# Sheet2.net
KiCad netlist of a schematic drawn in Altium Designer
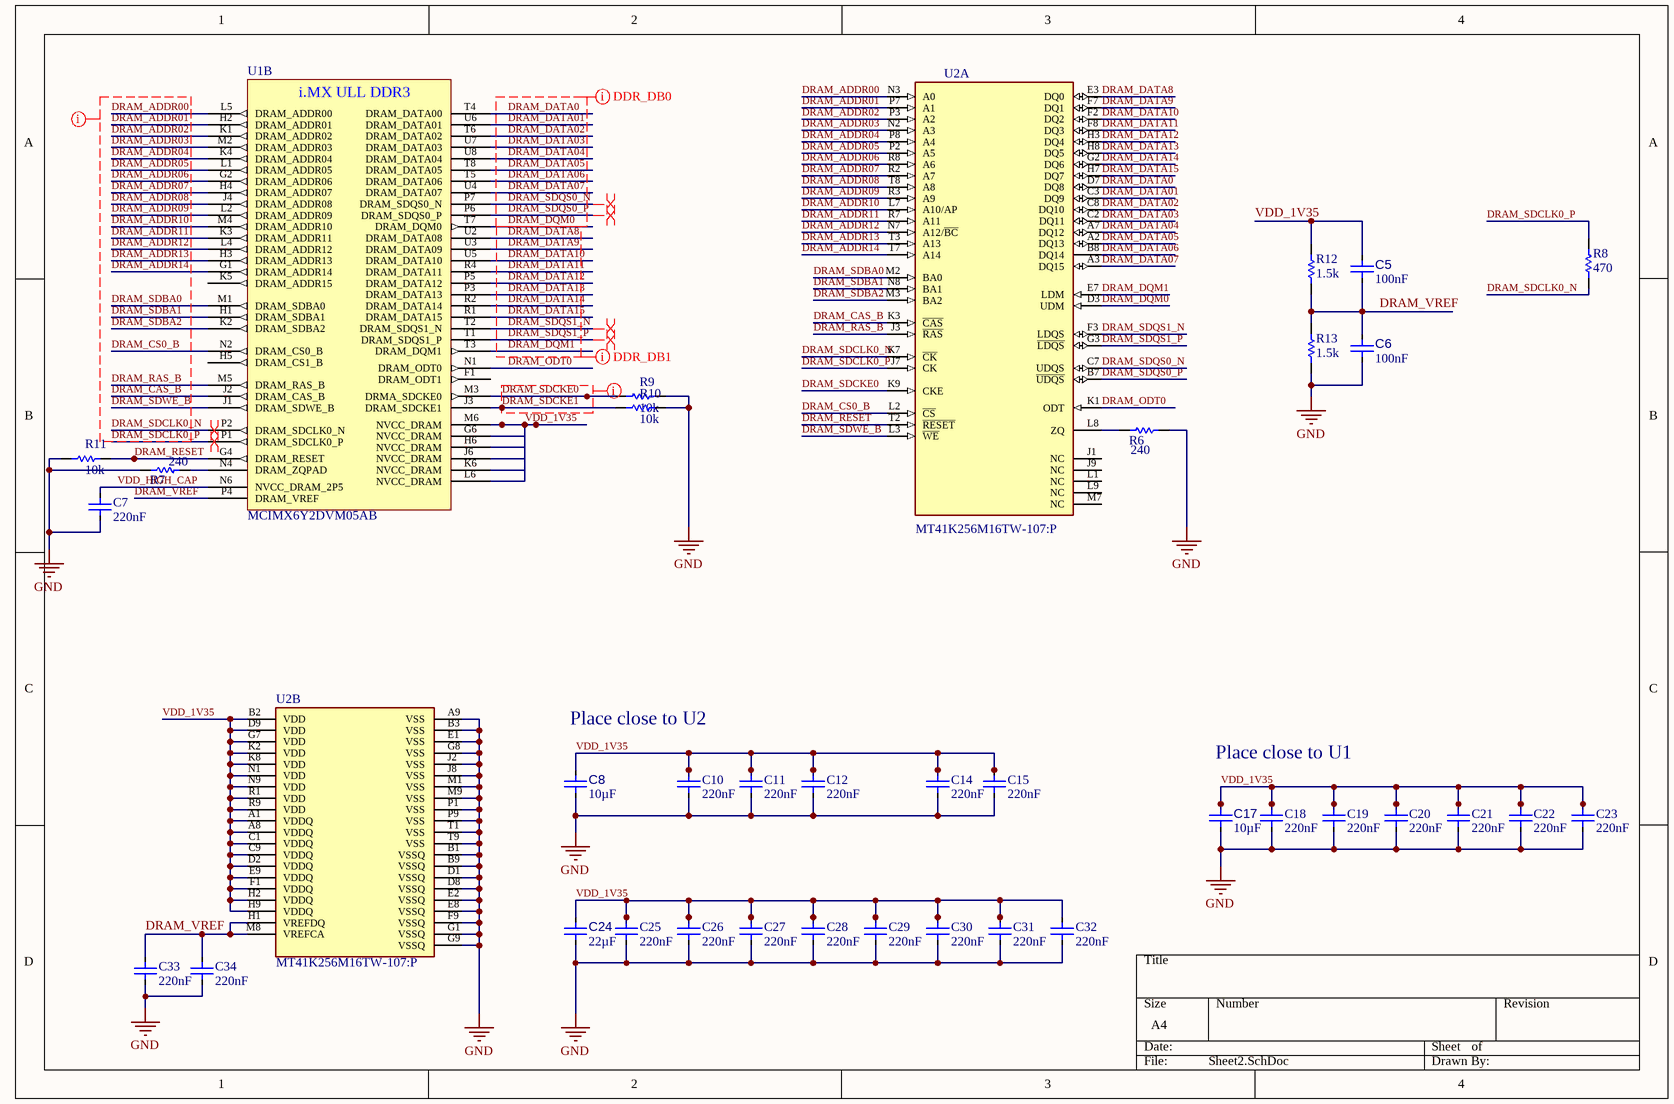
[diagram p0: Sheet2.SchDoc]

(export (version "E")
  (design (tool "Eeschema 10.0.6"))
  (components
    (comp (ref "C5")
      (value "100nF")
      (footprint "0402-SMD-CAP")
      (description "Chip Capacitor, 0.1 uF, +/- 5%, 16 V, 0402 (1005 Metric)")
      (fields (field (name "TOLERANCE") "5%") (field (name "MFR. PART NO.") "EMF105B7104MVHF"))
      (libsource (lib "Budapest University of Technology and Economics") (part "CAP-NP-2"))
    )
    (comp (ref "C6")
      (value "100nF")
      (footprint "0402-SMD-CAP")
      (description "Chip Capacitor, 0.1 uF, +/- 5%, 16 V, 0402 (1005 Metric)")
      (fields (field (name "TOLERANCE") "5%") (field (name "MFR. PART NO.") "EMF105B7104MVHF"))
      (libsource (lib "Budapest University of Technology and Economics") (part "CAP-NP-2"))
    )
    (comp (ref "C7")
      (value "220nF")
      (footprint "0402-SMD-CAP")
      (description "Chip Capacitor, 220nF +/-20%, 10V, 0402, Thickness 0.6 mm")
      (fields (field (name "TOLERANCE") "10%") (field (name "MFR. PART NO.") "0402ZD224KAT2A"))
      (libsource (lib "Budapest University of Technology and Economics") (part "b4654b650e69147ec39a6b967a45e02"))
    )
    (comp (ref "C8")
      (value "10µF")
      (footprint "0603-SMD-CAP")
      (description "Chip Capacitor, 10µF +/-20%, 10V, 0603, Thickness 1 mm")
      (fields (field (name "TOLERANCE") "10%") (field (name "MFR. PART NO.") "0603ZD106KAT2A"))
      (libsource (lib "Budapest University of Technology and Economics") (part "CAP-NP-2"))
    )
    (comp (ref "C10")
      (value "220nF")
      (footprint "0402-SMD-CAP")
      (description "Chip Capacitor, 220nF +/-20%, 10V, 0402, Thickness 0.6 mm")
      (fields (field (name "TOLERANCE") "10%") (field (name "MFR. PART NO.") "0402ZD224KAT2A"))
      (libsource (lib "Budapest University of Technology and Economics") (part "b4654b650e69147ec39a6b967a45e02"))
    )
    (comp (ref "C11")
      (value "220nF")
      (footprint "0402-SMD-CAP")
      (description "Chip Capacitor, 220nF +/-20%, 10V, 0402, Thickness 0.6 mm")
      (fields (field (name "TOLERANCE") "10%") (field (name "MFR. PART NO.") "0402ZD224KAT2A"))
      (libsource (lib "Budapest University of Technology and Economics") (part "b4654b650e69147ec39a6b967a45e02"))
    )
    (comp (ref "C12")
      (value "220nF")
      (footprint "0402-SMD-CAP")
      (description "Chip Capacitor, 220nF +/-20%, 10V, 0402, Thickness 0.6 mm")
      (fields (field (name "TOLERANCE") "10%") (field (name "MFR. PART NO.") "0402ZD224KAT2A"))
      (libsource (lib "Budapest University of Technology and Economics") (part "b4654b650e69147ec39a6b967a45e02"))
    )
    (comp (ref "C14")
      (value "220nF")
      (footprint "0402-SMD-CAP")
      (description "Chip Capacitor, 220nF +/-20%, 10V, 0402, Thickness 0.6 mm")
      (fields (field (name "TOLERANCE") "10%") (field (name "MFR. PART NO.") "0402ZD224KAT2A"))
      (libsource (lib "Budapest University of Technology and Economics") (part "b4654b650e69147ec39a6b967a45e02"))
    )
    (comp (ref "C15")
      (value "220nF")
      (footprint "0402-SMD-CAP")
      (description "Chip Capacitor, 220nF +/-20%, 10V, 0402, Thickness 0.6 mm")
      (fields (field (name "TOLERANCE") "10%") (field (name "MFR. PART NO.") "0402ZD224KAT2A"))
      (libsource (lib "Budapest University of Technology and Economics") (part "b4654b650e69147ec39a6b967a45e02"))
    )
    (comp (ref "C17")
      (value "10µF")
      (footprint "0603-SMD-CAP")
      (description "Chip Capacitor, 10µF +/-20%, 10V, 0603, Thickness 1 mm")
      (fields (field (name "TOLERANCE") "10%") (field (name "MFR. PART NO.") "0603ZD106KAT2A"))
      (libsource (lib "Budapest University of Technology and Economics") (part "CAP-NP-2"))
    )
    (comp (ref "C18")
      (value "220nF")
      (footprint "0402-SMD-CAP")
      (description "Chip Capacitor, 220nF +/-20%, 10V, 0402, Thickness 0.6 mm")
      (fields (field (name "TOLERANCE") "10%") (field (name "MFR. PART NO.") "0402ZD224KAT2A"))
      (libsource (lib "Budapest University of Technology and Economics") (part "b4654b650e69147ec39a6b967a45e02"))
    )
    (comp (ref "C19")
      (value "220nF")
      (footprint "0402-SMD-CAP")
      (description "Chip Capacitor, 220nF +/-20%, 10V, 0402, Thickness 0.6 mm")
      (fields (field (name "TOLERANCE") "10%") (field (name "MFR. PART NO.") "0402ZD224KAT2A"))
      (libsource (lib "Budapest University of Technology and Economics") (part "b4654b650e69147ec39a6b967a45e02"))
    )
    (comp (ref "C20")
      (value "220nF")
      (footprint "0402-SMD-CAP")
      (description "Chip Capacitor, 220nF +/-20%, 10V, 0402, Thickness 0.6 mm")
      (fields (field (name "TOLERANCE") "10%") (field (name "MFR. PART NO.") "0402ZD224KAT2A"))
      (libsource (lib "Budapest University of Technology and Economics") (part "b4654b650e69147ec39a6b967a45e02"))
    )
    (comp (ref "C21")
      (value "220nF")
      (footprint "0402-SMD-CAP")
      (description "Chip Capacitor, 220nF +/-20%, 10V, 0402, Thickness 0.6 mm")
      (fields (field (name "TOLERANCE") "10%") (field (name "MFR. PART NO.") "0402ZD224KAT2A"))
      (libsource (lib "Budapest University of Technology and Economics") (part "b4654b650e69147ec39a6b967a45e02"))
    )
    (comp (ref "C22")
      (value "220nF")
      (footprint "0402-SMD-CAP")
      (description "Chip Capacitor, 220nF +/-20%, 10V, 0402, Thickness 0.6 mm")
      (fields (field (name "TOLERANCE") "10%") (field (name "MFR. PART NO.") "0402ZD224KAT2A"))
      (libsource (lib "Budapest University of Technology and Economics") (part "b4654b650e69147ec39a6b967a45e02"))
    )
    (comp (ref "C23")
      (value "220nF")
      (footprint "0402-SMD-CAP")
      (description "Chip Capacitor, 220nF +/-20%, 10V, 0402, Thickness 0.6 mm")
      (fields (field (name "TOLERANCE") "10%") (field (name "MFR. PART NO.") "0402ZD224KAT2A"))
      (libsource (lib "Budapest University of Technology and Economics") (part "b4654b650e69147ec39a6b967a45e02"))
    )
    (comp (ref "C24")
      (value "22µF")
      (footprint "0805-SMD-CAP")
      (description "Chip Capacitor, 22µF +/-40%, 16V, 0805, Thickness 1.45 mm")
      (fields (field (name "TOLERANCE") "5%") (field (name "MFR. PART NO.") "CL21A226MOQNNNE"))
      (libsource (lib "Budapest University of Technology and Economics") (part "CAP-NP-2"))
    )
    (comp (ref "C25")
      (value "220nF")
      (footprint "0402-SMD-CAP")
      (description "Chip Capacitor, 220nF +/-20%, 10V, 0402, Thickness 0.6 mm")
      (fields (field (name "TOLERANCE") "10%") (field (name "MFR. PART NO.") "0402ZD224KAT2A"))
      (libsource (lib "Budapest University of Technology and Economics") (part "b4654b650e69147ec39a6b967a45e02"))
    )
    (comp (ref "C26")
      (value "220nF")
      (footprint "0402-SMD-CAP")
      (description "Chip Capacitor, 220nF +/-20%, 10V, 0402, Thickness 0.6 mm")
      (fields (field (name "TOLERANCE") "10%") (field (name "MFR. PART NO.") "0402ZD224KAT2A"))
      (libsource (lib "Budapest University of Technology and Economics") (part "b4654b650e69147ec39a6b967a45e02"))
    )
    (comp (ref "C27")
      (value "220nF")
      (footprint "0402-SMD-CAP")
      (description "Chip Capacitor, 220nF +/-20%, 10V, 0402, Thickness 0.6 mm")
      (fields (field (name "TOLERANCE") "10%") (field (name "MFR. PART NO.") "0402ZD224KAT2A"))
      (libsource (lib "Budapest University of Technology and Economics") (part "b4654b650e69147ec39a6b967a45e02"))
    )
    (comp (ref "C28")
      (value "220nF")
      (footprint "0402-SMD-CAP")
      (description "Chip Capacitor, 220nF +/-20%, 10V, 0402, Thickness 0.6 mm")
      (fields (field (name "TOLERANCE") "10%") (field (name "MFR. PART NO.") "0402ZD224KAT2A"))
      (libsource (lib "Budapest University of Technology and Economics") (part "b4654b650e69147ec39a6b967a45e02"))
    )
    (comp (ref "C29")
      (value "220nF")
      (footprint "0402-SMD-CAP")
      (description "Chip Capacitor, 220nF +/-20%, 10V, 0402, Thickness 0.6 mm")
      (fields (field (name "TOLERANCE") "10%") (field (name "MFR. PART NO.") "0402ZD224KAT2A"))
      (libsource (lib "Budapest University of Technology and Economics") (part "b4654b650e69147ec39a6b967a45e02"))
    )
    (comp (ref "C30")
      (value "220nF")
      (footprint "0402-SMD-CAP")
      (description "Chip Capacitor, 220nF +/-20%, 10V, 0402, Thickness 0.6 mm")
      (fields (field (name "TOLERANCE") "10%") (field (name "MFR. PART NO.") "0402ZD224KAT2A"))
      (libsource (lib "Budapest University of Technology and Economics") (part "b4654b650e69147ec39a6b967a45e02"))
    )
    (comp (ref "C31")
      (value "220nF")
      (footprint "0402-SMD-CAP")
      (description "Chip Capacitor, 220nF +/-20%, 10V, 0402, Thickness 0.6 mm")
      (fields (field (name "TOLERANCE") "10%") (field (name "MFR. PART NO.") "0402ZD224KAT2A"))
      (libsource (lib "Budapest University of Technology and Economics") (part "b4654b650e69147ec39a6b967a45e02"))
    )
    (comp (ref "C32")
      (value "220nF")
      (footprint "0402-SMD-CAP")
      (description "Chip Capacitor, 220nF +/-20%, 10V, 0402, Thickness 0.6 mm")
      (fields (field (name "TOLERANCE") "10%") (field (name "MFR. PART NO.") "0402ZD224KAT2A"))
      (libsource (lib "Budapest University of Technology and Economics") (part "b4654b650e69147ec39a6b967a45e02"))
    )
    (comp (ref "C33")
      (value "220nF")
      (footprint "0402-SMD-CAP")
      (description "Chip Capacitor, 220nF +/-20%, 10V, 0402, Thickness 0.6 mm")
      (fields (field (name "TOLERANCE") "10%") (field (name "MFR. PART NO.") "0402ZD224KAT2A"))
      (libsource (lib "Budapest University of Technology and Economics") (part "b4654b650e69147ec39a6b967a45e02"))
    )
    (comp (ref "C34")
      (value "220nF")
      (footprint "0402-SMD-CAP")
      (description "Chip Capacitor, 220nF +/-20%, 10V, 0402, Thickness 0.6 mm")
      (fields (field (name "TOLERANCE") "10%") (field (name "MFR. PART NO.") "0402ZD224KAT2A"))
      (libsource (lib "Budapest University of Technology and Economics") (part "b4654b650e69147ec39a6b967a45e02"))
    )
    (comp (ref "R6")
      (value "240")
      (footprint "0402_SMD_RES")
      (description "Res Thick Film 0402 240 Ohm 1% 0.063W(1/16W) ±100ppm/C Molded SMD Paper T/R")
      (fields (field (name "TOLERANCE") "1%") (field (name "Comment") "RC0402FR-07240RL"))
      (libsource (lib "Budapest University of Technology and Economics") (part "RES-2"))
    )
    (comp (ref "R7")
      (value "240")
      (footprint "0402_SMD_RES")
      (description "Res Thick Film 0402 240 Ohm 1% 0.063W(1/16W) ±100ppm/C Molded SMD Paper T/R")
      (fields (field (name "TOLERANCE") "1%") (field (name "Comment") "RC0402FR-07240RL"))
      (libsource (lib "Budapest University of Technology and Economics") (part "RES-2"))
    )
    (comp (ref "R8")
      (value "470")
      (footprint "0402_SMD_RES")
      (description "RES SMD 470 OHM 1% 1/16W 0402")
      (fields (field (name "POWER") "2.66W") (field (name "TOLERANCE") "1%"))
      (libsource (lib "Budapest University of Technology and Economics") (part "RES-2"))
    )
    (comp (ref "R9")
      (value "10k")
      (footprint "0402_SMD_RES")
      (description "Chip Resistor, 10 kOhms, +/-1 %, 63 mW, -55 to 125 degC, 0402")
      (fields (field (name "POWER") "63mW") (field (name "TOLERANCE") "1%"))
      (libsource (lib "Budapest University of Technology and Economics") (part "RES-2"))
    )
    (comp (ref "R10")
      (value "10k")
      (footprint "0402_SMD_RES")
      (description "Chip Resistor, 10 kOhms, +/-1 %, 63 mW, -55 to 125 degC, 0402")
      (fields (field (name "POWER") "63mW") (field (name "TOLERANCE") "1%"))
      (libsource (lib "Budapest University of Technology and Economics") (part "RES-2"))
    )
    (comp (ref "R11")
      (value "10k")
      (footprint "0402_SMD_RES")
      (description "Chip Resistor, 10 kOhms, +/-1 %, 63 mW, -55 to 125 degC, 0402")
      (fields (field (name "POWER") "63mW") (field (name "TOLERANCE") "1%"))
      (libsource (lib "Budapest University of Technology and Economics") (part "RES-2"))
    )
    (comp (ref "R12")
      (value "1.5k")
      (footprint "0402_SMD_RES")
      (description "PANASONIC - ERJ2RKF1501X - RES, 1K5, 1%, 0.1W, 0402, THICK FILM")
      (fields (field (name "TOLERANCE") "1%") (field (name "Comment") "ERJ-2RKF1501X"))
      (libsource (lib "Budapest University of Technology and Economics") (part "RES-2"))
    )
    (comp (ref "R13")
      (value "1.5k")
      (footprint "0402_SMD_RES")
      (description "PANASONIC - ERJ2RKF1501X - RES, 1K5, 1%, 0.1W, 0402, THICK FILM")
      (fields (field (name "TOLERANCE") "1%") (field (name "Comment") "ERJ-2RKF1501X"))
      (libsource (lib "Budapest University of Technology and Economics") (part "RES-2"))
    )
    (comp (ref "U1")
      (value "MCIMX6Y2DVM05AB")
      (footprint "BGA100P9X9-81A")
      (libsource (lib "Budapest University of Technology and Economics") (part "MCIMX6Y2DVM05AB"))
    )
    (comp (ref "U2")
      (value "MT41K256M16TW-107:P")
      (footprint "FP-TW-IPC_B")
      (description "DRAM Chip DDR3L SDRAM 4G-Bit 256Mx16 1.35V 96 FBGA")
      (libsource (lib "Budapest University of Technology and Economics") (part "cdaccbdf9e98e5f2804aaab7a1ea706"))
    )
  )
  (nets
    (net (code "1") (name "/DRAM_ADDR00") (class "Default")
      (node (ref "U1") (pin "L5") (pinfunction "DRAM_ADDR00_L5") (pintype "output"))
      (node (ref "U2") (pin "N3") (pinfunction "A0_N3") (pintype "input"))
    )
    (net (code "2") (name "/DRAM_ADDR01") (class "Default")
      (node (ref "U1") (pin "H2") (pinfunction "DRAM_ADDR01_H2") (pintype "output"))
      (node (ref "U2") (pin "P7") (pinfunction "A1_P7") (pintype "input"))
    )
    (net (code "3") (name "/DRAM_ADDR02") (class "Default")
      (node (ref "U1") (pin "K1") (pinfunction "DRAM_ADDR02_K1") (pintype "output"))
      (node (ref "U2") (pin "P3") (pinfunction "A2_P3") (pintype "input"))
    )
    (net (code "4") (name "/DRAM_ADDR03") (class "Default")
      (node (ref "U1") (pin "M2") (pinfunction "DRAM_ADDR03_M2") (pintype "output"))
      (node (ref "U2") (pin "N2") (pinfunction "A3_N2") (pintype "input"))
    )
    (net (code "5") (name "/DRAM_ADDR04") (class "Default")
      (node (ref "U1") (pin "K4") (pinfunction "DRAM_ADDR04_K4") (pintype "output"))
      (node (ref "U2") (pin "P8") (pinfunction "A4_P8") (pintype "input"))
    )
    (net (code "6") (name "/DRAM_ADDR05") (class "Default")
      (node (ref "U1") (pin "L1") (pinfunction "DRAM_ADDR05_L1") (pintype "output"))
      (node (ref "U2") (pin "P2") (pinfunction "A5_P2") (pintype "input"))
    )
    (net (code "7") (name "/DRAM_ADDR06") (class "Default")
      (node (ref "U1") (pin "G2") (pinfunction "DRAM_ADDR06_G2") (pintype "output"))
      (node (ref "U2") (pin "R8") (pinfunction "A6_R8") (pintype "input"))
    )
    (net (code "8") (name "/DRAM_ADDR07") (class "Default")
      (node (ref "U1") (pin "H4") (pinfunction "DRAM_ADDR07_H4") (pintype "output"))
      (node (ref "U2") (pin "R2") (pinfunction "A7_R2") (pintype "input"))
    )
    (net (code "9") (name "/DRAM_ADDR08") (class "Default")
      (node (ref "U1") (pin "J4") (pinfunction "DRAM_ADDR08_J4") (pintype "output"))
      (node (ref "U2") (pin "T8") (pinfunction "A8_T8") (pintype "input"))
    )
    (net (code "10") (name "/DRAM_ADDR09") (class "Default")
      (node (ref "U1") (pin "L2") (pinfunction "DRAM_ADDR09_L2") (pintype "output"))
      (node (ref "U2") (pin "R3") (pinfunction "A9_R3") (pintype "input"))
    )
    (net (code "11") (name "/DRAM_ADDR10") (class "Default")
      (node (ref "U1") (pin "M4") (pinfunction "DRAM_ADDR10_M4") (pintype "output"))
      (node (ref "U2") (pin "L7") (pinfunction "A10/AP_L7") (pintype "input"))
    )
    (net (code "12") (name "/DRAM_ADDR11") (class "Default")
      (node (ref "U1") (pin "K3") (pinfunction "DRAM_ADDR11_K3") (pintype "output"))
      (node (ref "U2") (pin "R7") (pinfunction "A11_R7") (pintype "input"))
    )
    (net (code "13") (name "/DRAM_ADDR12") (class "Default")
      (node (ref "U1") (pin "L4") (pinfunction "DRAM_ADDR12_L4") (pintype "output"))
      (node (ref "U2") (pin "N7") (pinfunction "A12/~{BC}_N7") (pintype "input"))
    )
    (net (code "14") (name "/DRAM_ADDR13") (class "Default")
      (node (ref "U1") (pin "H3") (pinfunction "DRAM_ADDR13_H3") (pintype "output"))
      (node (ref "U2") (pin "T3") (pinfunction "A13_T3") (pintype "input"))
    )
    (net (code "15") (name "/DRAM_ADDR14") (class "Default")
      (node (ref "U1") (pin "G1") (pinfunction "DRAM_ADDR14_G1") (pintype "output"))
      (node (ref "U2") (pin "T7") (pinfunction "A14_T7") (pintype "input"))
    )
    (net (code "16") (name "/DRAM_CAS_B") (class "Default")
      (node (ref "U1") (pin "J2") (pinfunction "DRAM_CAS_B_J2") (pintype "output"))
      (node (ref "U2") (pin "K3") (pinfunction "~{CAS}_K3") (pintype "input"))
    )
    (net (code "17") (name "/DRAM_CS0_B") (class "Default")
      (node (ref "U1") (pin "N2") (pinfunction "DRAM_CS0_B_N2") (pintype "output"))
      (node (ref "U2") (pin "L2") (pinfunction "~{CS}_L2") (pintype "input"))
    )
    (net (code "18") (name "/DRAM_DATA0") (class "Default")
      (node (ref "U1") (pin "T4") (pinfunction "DRAM_DATA00_T4") (pintype "passive"))
      (node (ref "U2") (pin "D7") (pinfunction "DQ8_D7") (pintype "bidirectional"))
    )
    (net (code "19") (name "/DRAM_DATA01") (class "Default")
      (node (ref "U1") (pin "U6") (pinfunction "DRAM_DATA01_U6") (pintype "passive"))
      (node (ref "U2") (pin "C3") (pinfunction "DQ9_C3") (pintype "bidirectional"))
    )
    (net (code "20") (name "/DRAM_DATA02") (class "Default")
      (node (ref "U1") (pin "T6") (pinfunction "DRAM_DATA02_T6") (pintype "passive"))
      (node (ref "U2") (pin "C8") (pinfunction "DQ10_C8") (pintype "bidirectional"))
    )
    (net (code "21") (name "/DRAM_DATA03") (class "Default")
      (node (ref "U1") (pin "U7") (pinfunction "DRAM_DATA03_U7") (pintype "passive"))
      (node (ref "U2") (pin "C2") (pinfunction "DQ11_C2") (pintype "bidirectional"))
    )
    (net (code "22") (name "/DRAM_DATA04") (class "Default")
      (node (ref "U1") (pin "U8") (pinfunction "DRAM_DATA04_U8") (pintype "passive"))
      (node (ref "U2") (pin "A7") (pinfunction "DQ12_A7") (pintype "bidirectional"))
    )
    (net (code "23") (name "/DRAM_DATA05") (class "Default")
      (node (ref "U1") (pin "T8") (pinfunction "DRAM_DATA05_T8") (pintype "passive"))
      (node (ref "U2") (pin "A2") (pinfunction "DQ13_A2") (pintype "bidirectional"))
    )
    (net (code "24") (name "/DRAM_DATA06") (class "Default")
      (node (ref "U1") (pin "T5") (pinfunction "DRAM_DATA06_T5") (pintype "passive"))
      (node (ref "U2") (pin "B8") (pinfunction "DQ14_B8") (pintype "power_in"))
    )
    (net (code "25") (name "/DRAM_DATA07") (class "Default")
      (node (ref "U1") (pin "U4") (pinfunction "DRAM_DATA07_U4") (pintype "passive"))
      (node (ref "U2") (pin "A3") (pinfunction "DQ15_A3") (pintype "bidirectional"))
    )
    (net (code "26") (name "/DRAM_DATA8") (class "Default")
      (node (ref "U1") (pin "U2") (pinfunction "DRAM_DATA08_U2") (pintype "passive"))
      (node (ref "U2") (pin "E3") (pinfunction "DQ0_E3") (pintype "bidirectional"))
    )
    (net (code "27") (name "/DRAM_DATA9") (class "Default")
      (node (ref "U1") (pin "U3") (pinfunction "DRAM_DATA09_U3") (pintype "passive"))
      (node (ref "U2") (pin "F7") (pinfunction "DQ1_F7") (pintype "bidirectional"))
    )
    (net (code "28") (name "/DRAM_DATA10") (class "Default")
      (node (ref "U1") (pin "U5") (pinfunction "DRAM_DATA10_U5") (pintype "passive"))
      (node (ref "U2") (pin "F2") (pinfunction "DQ2_F2") (pintype "bidirectional"))
    )
    (net (code "29") (name "/DRAM_DATA11") (class "Default")
      (node (ref "U1") (pin "R4") (pinfunction "DRAM_DATA11_R4") (pintype "passive"))
      (node (ref "U2") (pin "F8") (pinfunction "DQ3_F8") (pintype "bidirectional"))
    )
    (net (code "30") (name "/DRAM_DATA12") (class "Default")
      (node (ref "U1") (pin "P5") (pinfunction "DRAM_DATA12_P5") (pintype "passive"))
      (node (ref "U2") (pin "H3") (pinfunction "DQ4_H3") (pintype "bidirectional"))
    )
    (net (code "31") (name "/DRAM_DATA13") (class "Default")
      (node (ref "U1") (pin "P3") (pinfunction "DRAM_DATA13_P3") (pintype "passive"))
      (node (ref "U2") (pin "H8") (pinfunction "DQ5_H8") (pintype "bidirectional"))
    )
    (net (code "32") (name "/DRAM_DATA14") (class "Default")
      (node (ref "U1") (pin "R2") (pinfunction "DRAM_DATA14_R2") (pintype "passive"))
      (node (ref "U2") (pin "G2") (pinfunction "DQ6_G2") (pintype "bidirectional"))
    )
    (net (code "33") (name "/DRAM_DATA15") (class "Default")
      (node (ref "U1") (pin "R1") (pinfunction "DRAM_DATA15_R1") (pintype "passive"))
      (node (ref "U2") (pin "H7") (pinfunction "DQ7_H7") (pintype "bidirectional"))
    )
    (net (code "34") (name "/DRAM_DQM0") (class "Default")
      (node (ref "U1") (pin "T7") (pinfunction "DRAM_DQM0_T7") (pintype "output"))
      (node (ref "U2") (pin "D3") (pinfunction "UDM_D3") (pintype "input"))
    )
    (net (code "35") (name "/DRAM_DQM1") (class "Default")
      (node (ref "U1") (pin "T3") (pinfunction "DRAM_DQM1_T3") (pintype "output"))
      (node (ref "U2") (pin "E7") (pinfunction "LDM_E7") (pintype "input"))
    )
    (net (code "36") (name "/DRAM_ODT0") (class "Default")
      (node (ref "U1") (pin "N1") (pinfunction "DRAM_ODT0_N1") (pintype "output"))
      (node (ref "U2") (pin "K1") (pinfunction "ODT_K1") (pintype "input"))
    )
    (net (code "37") (name "/DRAM_RAS_B") (class "Default")
      (node (ref "U1") (pin "M5") (pinfunction "DRAM_RAS_B_M5") (pintype "output"))
      (node (ref "U2") (pin "J3") (pinfunction "~{RAS}_J3") (pintype "input"))
    )
    (net (code "38") (name "/DRAM_RESET") (class "Default")
      (node (ref "R11") (pin "2") (pinfunction "2_2") (pintype "passive"))
      (node (ref "U1") (pin "G4") (pinfunction "DRAM_RESET_G4") (pintype "output"))
      (node (ref "U2") (pin "T2") (pinfunction "~{RESET}_T2") (pintype "input"))
    )
    (net (code "39") (name "/DRAM_SDBA0") (class "Default")
      (node (ref "U1") (pin "M1") (pinfunction "DRAM_SDBA0_M1") (pintype "output"))
      (node (ref "U2") (pin "M2") (pinfunction "BA0_M2") (pintype "input"))
    )
    (net (code "40") (name "/DRAM_SDBA1") (class "Default")
      (node (ref "U1") (pin "H1") (pinfunction "DRAM_SDBA1_H1") (pintype "output"))
      (node (ref "U2") (pin "N8") (pinfunction "BA1_N8") (pintype "input"))
    )
    (net (code "41") (name "/DRAM_SDBA2") (class "Default")
      (node (ref "U1") (pin "K2") (pinfunction "DRAM_SDBA2_K2") (pintype "output"))
      (node (ref "U2") (pin "M3") (pinfunction "BA2_M3") (pintype "input"))
    )
    (net (code "42") (name "/DRAM_SDCKE0") (class "Default")
      (node (ref "R9") (pin "1") (pinfunction "1_1") (pintype "passive"))
      (node (ref "U1") (pin "M3") (pinfunction "DRMA_SDCKE0_M3") (pintype "output"))
      (node (ref "U2") (pin "K9") (pinfunction "CKE_K9") (pintype "input"))
    )
    (net (code "43") (name "/DRAM_SDCKE1") (class "Default")
      (node (ref "R10") (pin "1") (pinfunction "1_1") (pintype "passive"))
      (node (ref "U1") (pin "J3") (pinfunction "DRAM_SDCKE1_J3") (pintype "passive"))
    )
    (net (code "44") (name "/DRAM_SDCLK0_N") (class "Default")
      (node (ref "R8") (pin "1") (pinfunction "1_1") (pintype "passive"))
      (node (ref "U1") (pin "P2") (pinfunction "DRAM_SDCLK0_N_P2") (pintype "output"))
      (node (ref "U2") (pin "K7") (pinfunction "~{CK}_K7") (pintype "input"))
    )
    (net (code "45") (name "/DRAM_SDCLK0_P") (class "Default")
      (node (ref "R8") (pin "2") (pinfunction "2_2") (pintype "passive"))
      (node (ref "U1") (pin "P1") (pinfunction "DRAM_SDCLK0_P_P1") (pintype "output"))
      (node (ref "U2") (pin "J7") (pinfunction "CK_J7") (pintype "input"))
    )
    (net (code "46") (name "/DRAM_SDQS0_N") (class "Default")
      (node (ref "U1") (pin "P7") (pinfunction "DRAM_SDQS0_N_P7") (pintype "passive"))
      (node (ref "U2") (pin "C7") (pinfunction "UDQS_C7") (pintype "bidirectional"))
    )
    (net (code "47") (name "/DRAM_SDQS0_P") (class "Default")
      (node (ref "U1") (pin "P6") (pinfunction "DRAM_SDQS0_P_P6") (pintype "passive"))
      (node (ref "U2") (pin "B7") (pinfunction "~{UDQS}_B7") (pintype "bidirectional"))
    )
    (net (code "48") (name "/DRAM_SDQS1_N") (class "Default")
      (node (ref "U1") (pin "T2") (pinfunction "DRAM_SDQS1_N_T2") (pintype "passive"))
      (node (ref "U2") (pin "F3") (pinfunction "LDQS_F3") (pintype "bidirectional"))
    )
    (net (code "49") (name "/DRAM_SDQS1_P") (class "Default")
      (node (ref "U1") (pin "T1") (pinfunction "DRAM_SDQS1_P_T1") (pintype "passive"))
      (node (ref "U2") (pin "G3") (pinfunction "~{LDQS}_G3") (pintype "bidirectional"))
    )
    (net (code "50") (name "/DRAM_SDWE_B") (class "Default")
      (node (ref "U1") (pin "J1") (pinfunction "DRAM_SDWE_B_J1") (pintype "output"))
      (node (ref "U2") (pin "L3") (pinfunction "~{WE}_L3") (pintype "input"))
    )
    (net (code "51") (name "/DRAM_VREF") (class "Default")
      (node (ref "C33") (pin "2") (pinfunction "2_2") (pintype "passive"))
      (node (ref "C34") (pin "2") (pinfunction "2_2") (pintype "passive"))
      (node (ref "C5") (pin "1") (pinfunction "1_1") (pintype "passive"))
      (node (ref "C6") (pin "2") (pinfunction "2_2") (pintype "passive"))
      (node (ref "R12") (pin "1") (pinfunction "1_1") (pintype "passive"))
      (node (ref "R13") (pin "2") (pinfunction "2_2") (pintype "passive"))
      (node (ref "U1") (pin "P4") (pinfunction "DRAM_VREF_P4") (pintype "passive"))
      (node (ref "U2") (pin "H1") (pinfunction "VREFDQ_H1") (pintype "power_in"))
      (node (ref "U2") (pin "M8") (pinfunction "VREFCA_M8") (pintype "power_in"))
    )
    (net (code "52") (name "/VDD_1V35") (class "Default")
      (node (ref "C10") (pin "2") (pinfunction "2_2") (pintype "passive"))
      (node (ref "C11") (pin "2") (pinfunction "2_2") (pintype "passive"))
      (node (ref "C12") (pin "2") (pinfunction "2_2") (pintype "passive"))
      (node (ref "C14") (pin "2") (pinfunction "2_2") (pintype "passive"))
      (node (ref "C15") (pin "2") (pinfunction "2_2") (pintype "passive"))
      (node (ref "C17") (pin "2") (pinfunction "2_2") (pintype "passive"))
      (node (ref "C18") (pin "2") (pinfunction "2_2") (pintype "passive"))
      (node (ref "C19") (pin "2") (pinfunction "2_2") (pintype "passive"))
      (node (ref "C20") (pin "2") (pinfunction "2_2") (pintype "passive"))
      (node (ref "C21") (pin "2") (pinfunction "2_2") (pintype "passive"))
      (node (ref "C22") (pin "2") (pinfunction "2_2") (pintype "passive"))
      (node (ref "C23") (pin "2") (pinfunction "2_2") (pintype "passive"))
      (node (ref "C24") (pin "2") (pinfunction "2_2") (pintype "passive"))
      (node (ref "C25") (pin "2") (pinfunction "2_2") (pintype "passive"))
      (node (ref "C26") (pin "2") (pinfunction "2_2") (pintype "passive"))
      (node (ref "C27") (pin "2") (pinfunction "2_2") (pintype "passive"))
      (node (ref "C28") (pin "2") (pinfunction "2_2") (pintype "passive"))
      (node (ref "C29") (pin "2") (pinfunction "2_2") (pintype "passive"))
      (node (ref "C30") (pin "2") (pinfunction "2_2") (pintype "passive"))
      (node (ref "C31") (pin "2") (pinfunction "2_2") (pintype "passive"))
      (node (ref "C32") (pin "2") (pinfunction "2_2") (pintype "passive"))
      (node (ref "C5") (pin "2") (pinfunction "2_2") (pintype "passive"))
      (node (ref "C8") (pin "2") (pinfunction "2_2") (pintype "passive"))
      (node (ref "R12") (pin "2") (pinfunction "2_2") (pintype "passive"))
      (node (ref "U1") (pin "G6") (pinfunction "NVCC_DRAM_G6") (pintype "passive"))
      (node (ref "U1") (pin "H6") (pinfunction "NVCC_DRAM_H6") (pintype "passive"))
      (node (ref "U1") (pin "J6") (pinfunction "NVCC_DRAM_J6") (pintype "passive"))
      (node (ref "U1") (pin "K6") (pinfunction "NVCC_DRAM_K6") (pintype "passive"))
      (node (ref "U1") (pin "L6") (pinfunction "NVCC_DRAM_L6") (pintype "passive"))
      (node (ref "U1") (pin "M6") (pinfunction "NVCC_DRAM_M6") (pintype "passive"))
      (node (ref "U2") (pin "A1") (pinfunction "VDDQ_A1") (pintype "power_in"))
      (node (ref "U2") (pin "A8") (pinfunction "VDDQ_A8") (pintype "power_in"))
      (node (ref "U2") (pin "B2") (pinfunction "VDD_B2") (pintype "power_in"))
      (node (ref "U2") (pin "C1") (pinfunction "VDDQ_C1") (pintype "power_in"))
      (node (ref "U2") (pin "C9") (pinfunction "VDDQ_C9") (pintype "power_in"))
      (node (ref "U2") (pin "D2") (pinfunction "VDDQ_D2") (pintype "power_in"))
      (node (ref "U2") (pin "D9") (pinfunction "VDD_D9") (pintype "power_in"))
      (node (ref "U2") (pin "E9") (pinfunction "VDDQ_E9") (pintype "power_in"))
      (node (ref "U2") (pin "F1") (pinfunction "VDDQ_F1") (pintype "power_in"))
      (node (ref "U2") (pin "G7") (pinfunction "VDD_G7") (pintype "power_in"))
      (node (ref "U2") (pin "H2") (pinfunction "VDDQ_H2") (pintype "power_in"))
      (node (ref "U2") (pin "H9") (pinfunction "VDDQ_H9") (pintype "power_in"))
      (node (ref "U2") (pin "K2") (pinfunction "VDD_K2") (pintype "power_in"))
      (node (ref "U2") (pin "K8") (pinfunction "VDD_K8") (pintype "power_in"))
      (node (ref "U2") (pin "N1") (pinfunction "VDD_N1") (pintype "power_in"))
      (node (ref "U2") (pin "N9") (pinfunction "VDD_N9") (pintype "power_in"))
      (node (ref "U2") (pin "R1") (pinfunction "VDD_R1") (pintype "power_in"))
      (node (ref "U2") (pin "R9") (pinfunction "VDD_R9") (pintype "power_in"))
    )
    (net (code "53") (name "/VDD_HIGH_CAP") (class "Default")
      (node (ref "C7") (pin "2") (pinfunction "2_2") (pintype "passive"))
      (node (ref "U1") (pin "N6") (pinfunction "NVCC_DRAM_2P5_N6") (pintype "passive"))
    )
    (net (code "54") (name "GND") (class "Default")
      (node (ref "C10") (pin "1") (pinfunction "1_1") (pintype "passive"))
      (node (ref "C11") (pin "1") (pinfunction "1_1") (pintype "passive"))
      (node (ref "C12") (pin "1") (pinfunction "1_1") (pintype "passive"))
      (node (ref "C14") (pin "1") (pinfunction "1_1") (pintype "passive"))
      (node (ref "C15") (pin "1") (pinfunction "1_1") (pintype "passive"))
      (node (ref "C17") (pin "1") (pinfunction "1_1") (pintype "passive"))
      (node (ref "C18") (pin "1") (pinfunction "1_1") (pintype "passive"))
      (node (ref "C19") (pin "1") (pinfunction "1_1") (pintype "passive"))
      (node (ref "C20") (pin "1") (pinfunction "1_1") (pintype "passive"))
      (node (ref "C21") (pin "1") (pinfunction "1_1") (pintype "passive"))
      (node (ref "C22") (pin "1") (pinfunction "1_1") (pintype "passive"))
      (node (ref "C23") (pin "1") (pinfunction "1_1") (pintype "passive"))
      (node (ref "C24") (pin "1") (pinfunction "1_1") (pintype "passive"))
      (node (ref "C25") (pin "1") (pinfunction "1_1") (pintype "passive"))
      (node (ref "C26") (pin "1") (pinfunction "1_1") (pintype "passive"))
      (node (ref "C27") (pin "1") (pinfunction "1_1") (pintype "passive"))
      (node (ref "C28") (pin "1") (pinfunction "1_1") (pintype "passive"))
      (node (ref "C29") (pin "1") (pinfunction "1_1") (pintype "passive"))
      (node (ref "C30") (pin "1") (pinfunction "1_1") (pintype "passive"))
      (node (ref "C31") (pin "1") (pinfunction "1_1") (pintype "passive"))
      (node (ref "C32") (pin "1") (pinfunction "1_1") (pintype "passive"))
      (node (ref "C33") (pin "1") (pinfunction "1_1") (pintype "passive"))
      (node (ref "C34") (pin "1") (pinfunction "1_1") (pintype "passive"))
      (node (ref "C6") (pin "1") (pinfunction "1_1") (pintype "passive"))
      (node (ref "C7") (pin "1") (pinfunction "1_1") (pintype "passive"))
      (node (ref "C8") (pin "1") (pinfunction "1_1") (pintype "passive"))
      (node (ref "R10") (pin "2") (pinfunction "2_2") (pintype "passive"))
      (node (ref "R11") (pin "1") (pinfunction "1_1") (pintype "passive"))
      (node (ref "R13") (pin "1") (pinfunction "1_1") (pintype "passive"))
      (node (ref "R6") (pin "2") (pinfunction "2_2") (pintype "passive"))
      (node (ref "R7") (pin "1") (pinfunction "1_1") (pintype "passive"))
      (node (ref "R9") (pin "2") (pinfunction "2_2") (pintype "passive"))
      (node (ref "U2") (pin "A9") (pinfunction "VSS_A9") (pintype "power_in"))
      (node (ref "U2") (pin "B1") (pinfunction "VSSQ_B1") (pintype "power_in"))
      (node (ref "U2") (pin "B3") (pinfunction "VSS_B3") (pintype "power_in"))
      (node (ref "U2") (pin "B9") (pinfunction "VSSQ_B9") (pintype "power_in"))
      (node (ref "U2") (pin "D1") (pinfunction "VSSQ_D1") (pintype "power_in"))
      (node (ref "U2") (pin "D8") (pinfunction "VSSQ_D8") (pintype "power_in"))
      (node (ref "U2") (pin "E1") (pinfunction "VSS_E1") (pintype "power_in"))
      (node (ref "U2") (pin "E2") (pinfunction "VSSQ_E2") (pintype "power_in"))
      (node (ref "U2") (pin "E8") (pinfunction "VSSQ_E8") (pintype "power_in"))
      (node (ref "U2") (pin "F9") (pinfunction "VSSQ_F9") (pintype "power_in"))
      (node (ref "U2") (pin "G1") (pinfunction "VSSQ_G1") (pintype "power_in"))
      (node (ref "U2") (pin "G8") (pinfunction "VSS_G8") (pintype "power_in"))
      (node (ref "U2") (pin "G9") (pinfunction "VSSQ_G9") (pintype "power_in"))
      (node (ref "U2") (pin "J2") (pinfunction "VSS_J2") (pintype "power_in"))
      (node (ref "U2") (pin "J8") (pinfunction "VSS_J8") (pintype "power_in"))
      (node (ref "U2") (pin "M1") (pinfunction "VSS_M1") (pintype "power_in"))
      (node (ref "U2") (pin "M9") (pinfunction "VSS_M9") (pintype "power_in"))
      (node (ref "U2") (pin "P1") (pinfunction "VSS_P1") (pintype "power_in"))
      (node (ref "U2") (pin "P9") (pinfunction "VSS_P9") (pintype "power_in"))
      (node (ref "U2") (pin "T1") (pinfunction "VSS_T1") (pintype "power_in"))
      (node (ref "U2") (pin "T9") (pinfunction "VSS_T9") (pintype "power_in"))
    )
    (net (code "55") (name "Net-(U1B-DRAM_ZQPAD)") (class "Default")
      (node (ref "R7") (pin "2") (pinfunction "2_2") (pintype "passive"))
      (node (ref "U1") (pin "N4") (pinfunction "DRAM_ZQPAD_N4") (pintype "passive"))
    )
    (net (code "56") (name "Net-(U2A-ZQ)") (class "Default")
      (node (ref "R6") (pin "1") (pinfunction "1_1") (pintype "passive"))
      (node (ref "U2") (pin "L8") (pinfunction "ZQ_L8") (pintype "passive"))
    )
    (net (code "57") (name "unconnected-(U1B-DRAM_ADDR15-PadK5)") (class "Default")
      (node (ref "U1") (pin "K5") (pinfunction "DRAM_ADDR15_K5") (pintype "output"))
    )
    (net (code "58") (name "unconnected-(U1B-DRAM_CS1_B-PadH5)") (class "Default")
      (node (ref "U1") (pin "H5") (pinfunction "DRAM_CS1_B_H5") (pintype "output"))
    )
    (net (code "59") (name "unconnected-(U1B-DRAM_ODT1-PadF1)") (class "Default")
      (node (ref "U1") (pin "F1") (pinfunction "DRAM_ODT1_F1") (pintype "output"))
    )
    (net (code "60") (name "unconnected-(U2A-NC-PadJ1)") (class "Default")
      (node (ref "U2") (pin "J1") (pinfunction "NC_J1") (pintype "passive"))
    )
    (net (code "61") (name "unconnected-(U2A-NC-PadJ9)") (class "Default")
      (node (ref "U2") (pin "J9") (pinfunction "NC_J9") (pintype "passive"))
    )
    (net (code "62") (name "unconnected-(U2A-NC-PadL1)") (class "Default")
      (node (ref "U2") (pin "L1") (pinfunction "NC_L1") (pintype "passive"))
    )
    (net (code "63") (name "unconnected-(U2A-NC-PadL9)") (class "Default")
      (node (ref "U2") (pin "L9") (pinfunction "NC_L9") (pintype "passive"))
    )
    (net (code "64") (name "unconnected-(U2A-NC-PadM7)") (class "Default")
      (node (ref "U2") (pin "M7") (pinfunction "NC_M7") (pintype "passive"))
    )
  )
)
